# main_board.net
KiCad netlist of a schematic drawn in EAGLE
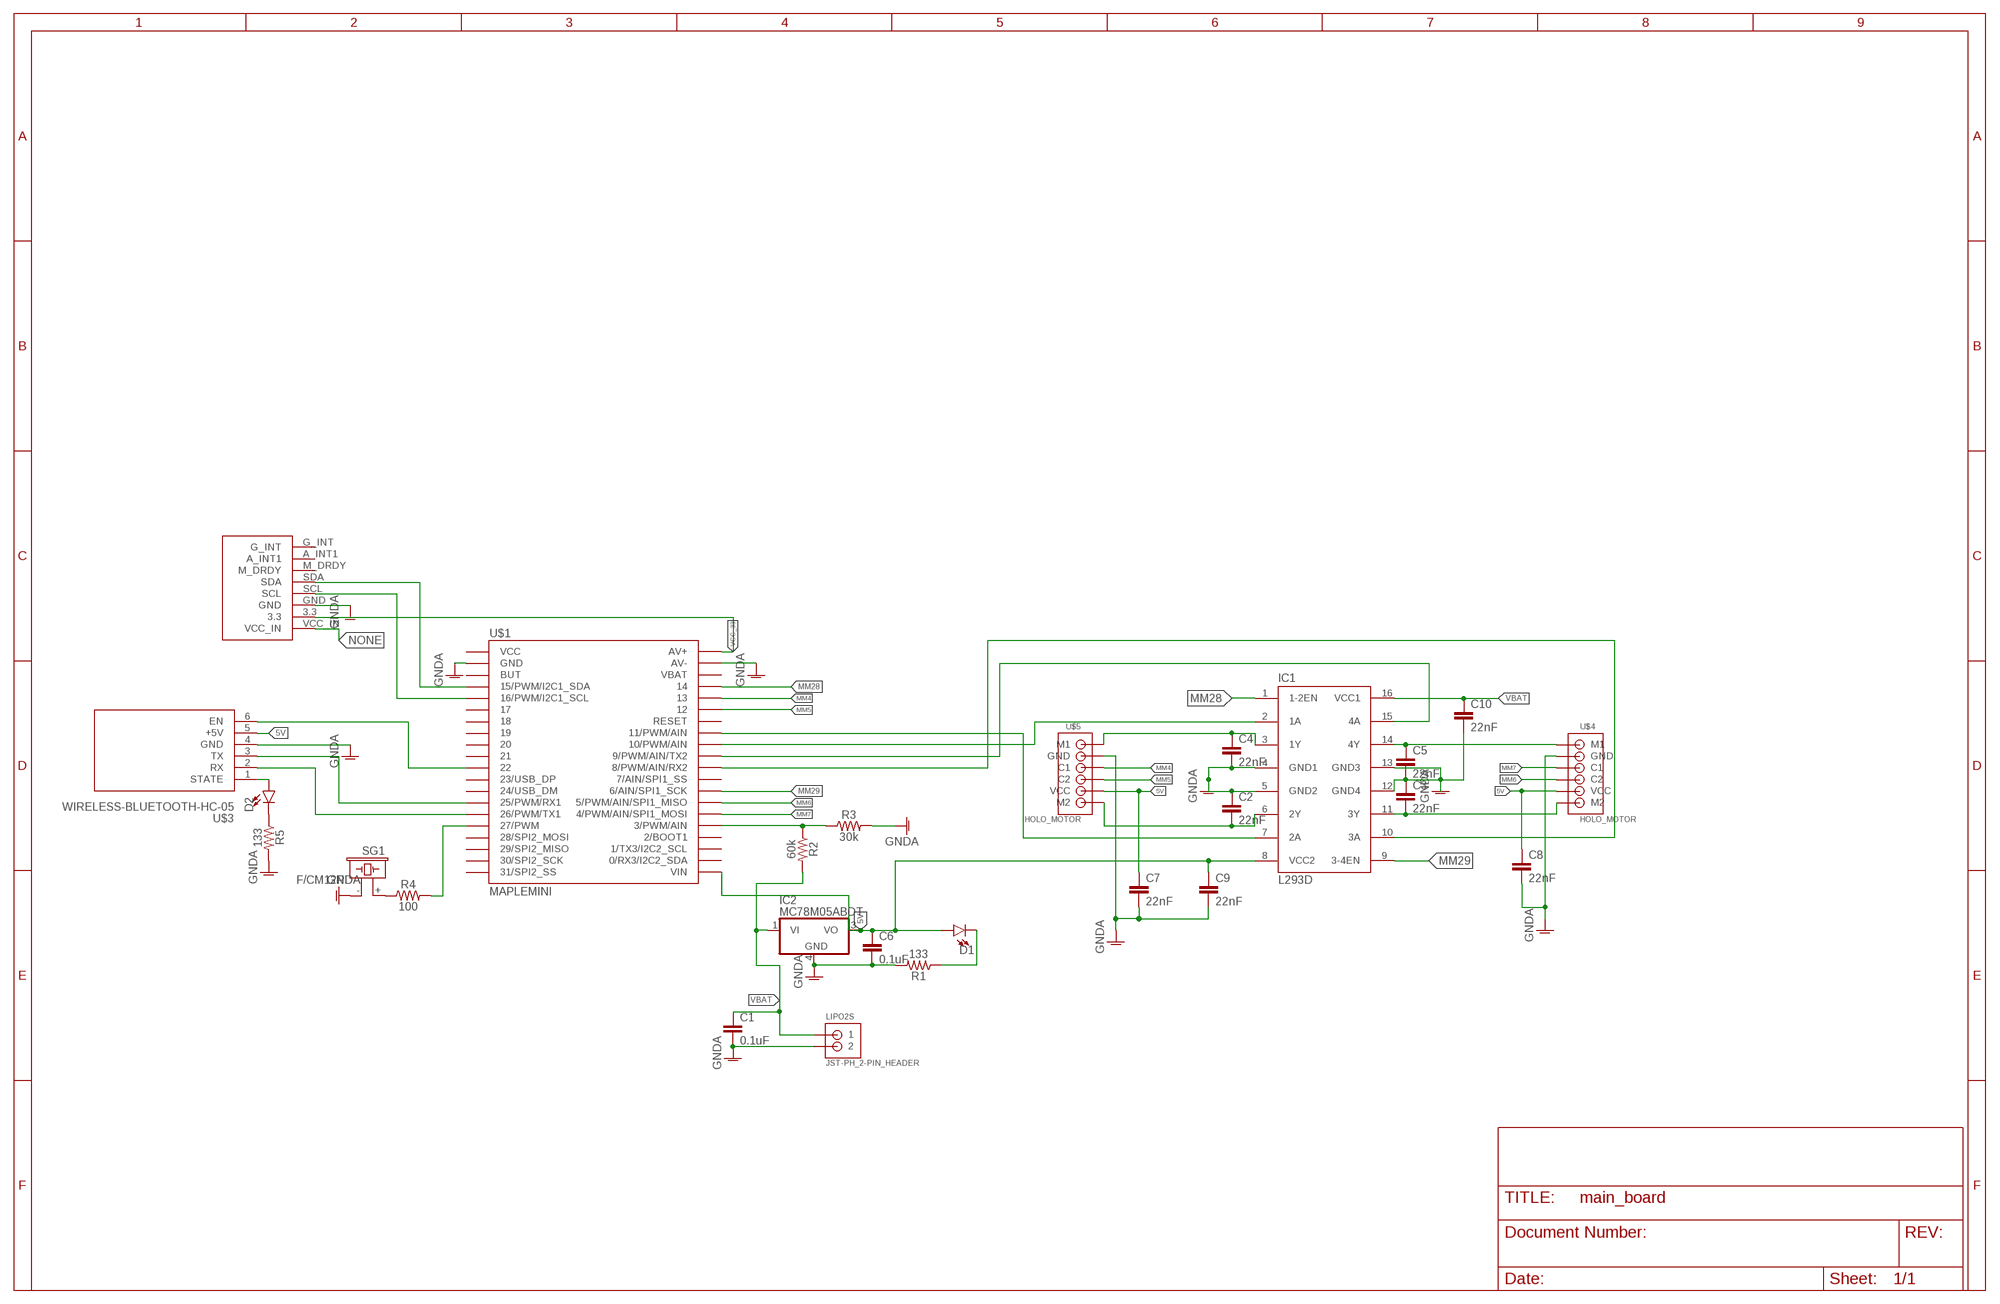
[diagram p0: schematic, sheet 1]

(export (version "E")
  (design (tool "Eeschema 10.0.6"))
  (components
    (comp (ref "C1")
      (value "0.1uF")
      (footprint "eagle-import:0603")
      (libsource (lib "eagle-import") (part "0.1UF-0603-25V-(+80/-20%)"))
    )
    (comp (ref "C2")
      (value "22nF")
      (footprint "eagle-import:0603")
      (libsource (lib "eagle-import") (part "22NF/22,000PF-0603-50V-10%"))
    )
    (comp (ref "C3")
      (value "22nF")
      (footprint "eagle-import:0603")
      (libsource (lib "eagle-import") (part "22NF/22,000PF-0603-50V-10%"))
    )
    (comp (ref "C4")
      (value "22nF")
      (footprint "eagle-import:0603")
      (libsource (lib "eagle-import") (part "22NF/22,000PF-0603-50V-10%"))
    )
    (comp (ref "C5")
      (value "22nF")
      (footprint "eagle-import:0603")
      (libsource (lib "eagle-import") (part "22NF/22,000PF-0603-50V-10%"))
    )
    (comp (ref "C6")
      (value "0.1uF")
      (footprint "eagle-import:0603")
      (libsource (lib "eagle-import") (part "0.1UF-0603-25V-(+80/-20%)"))
    )
    (comp (ref "C7")
      (value "22nF")
      (footprint "eagle-import:0603")
      (fields (field (name "PROD_ID") "CAP-07885"))
      (libsource (lib "eagle-import") (part "22NF/22,000PF-0603-50V-10%"))
    )
    (comp (ref "C8")
      (value "22nF")
      (footprint "eagle-import:0603")
      (fields (field (name "PROD_ID") "CAP-07885"))
      (libsource (lib "eagle-import") (part "22NF/22,000PF-0603-50V-10%"))
    )
    (comp (ref "C9")
      (value "22nF")
      (footprint "eagle-import:0603")
      (fields (field (name "PROD_ID") "CAP-07885"))
      (libsource (lib "eagle-import") (part "22NF/22,000PF-0603-50V-10%"))
    )
    (comp (ref "C10")
      (value "22nF")
      (footprint "eagle-import:0603")
      (fields (field (name "PROD_ID") "CAP-07885"))
      (libsource (lib "eagle-import") (part "22NF/22,000PF-0603-50V-10%"))
    )
    (comp (ref "D1")
      (value "LED-FKIT-1206")
      (footprint "eagle-import:FKIT-LED-1206")
      (libsource (lib "eagle-import") (part "LED-FKIT-1206"))
    )
    (comp (ref "D2")
      (value "LED-FKIT-1206")
      (footprint "eagle-import:FKIT-LED-1206")
      (libsource (lib "eagle-import") (part "LED-FKIT-1206"))
    )
    (comp (ref "IC1")
      (value "L293D")
      (footprint "eagle-import:DIL16")
      (libsource (lib "eagle-import") (part "L293D"))
    )
    (comp (ref "IC2")
      (value "MC78M05ABDT")
      (footprint "eagle-import:DPACK_3")
      (libsource (lib "eagle-import") (part "MC78M05ABDT"))
    )
    (comp (ref "LIPO2S")
      (value "JST-PH_2-PIN_HEADER")
      (footprint "eagle-import:JST_B2B-PH_HEADER")
      (libsource (lib "eagle-import") (part "JST-PH_2-PIN_HEADER"))
    )
    (comp (ref "R1")
      (value "133")
      (footprint "eagle-import:0603")
      (libsource (lib "eagle-import") (part "0.27OHM-0603-1/10W-1%"))
    )
    (comp (ref "R2")
      (value "60k")
      (footprint "eagle-import:0603")
      (libsource (lib "eagle-import") (part "0.27OHM-0603-1/10W-1%"))
    )
    (comp (ref "R3")
      (value "30k")
      (footprint "eagle-import:0603")
      (libsource (lib "eagle-import") (part "0.27OHM-0603-1/10W-1%"))
    )
    (comp (ref "R4")
      (value "100")
      (footprint "eagle-import:0603")
      (libsource (lib "eagle-import") (part "0.27OHM-0603-1/10W-1%"))
    )
    (comp (ref "R5")
      (value "133")
      (footprint "eagle-import:0603")
      (libsource (lib "eagle-import") (part "0.27OHM-0603-1/10W-1%"))
    )
    (comp (ref "SG1")
      (value "F/CM12P")
      (footprint "eagle-import:F_CM12P")
      (libsource (lib "eagle-import") (part "F/CM12P"))
    )
    (comp (ref "U$1")
      (value "MAPLEMINI")
      (footprint "eagle-import:20-DIP")
      (libsource (lib "eagle-import") (part "MAPLEMINI"))
    )
    (comp (ref "U$3")
      (value "WIRELESS-BLUETOOTH-HC-05")
      (footprint "eagle-import:WIRELESS-BLUETOOTH-HC-05")
      (libsource (lib "eagle-import") (part "WIRELESS-BLUETOOTH-HC-05"))
    )
    (comp (ref "U$4")
      (value "HOLO_MOTOR")
      (footprint "eagle-import:HOLO_MOTOR")
      (libsource (lib "eagle-import") (part "HOLO_MOTOR"))
    )
    (comp (ref "U$5")
      (value "HOLO_MOTOR")
      (footprint "eagle-import:HOLO_MOTOR")
      (libsource (lib "eagle-import") (part "HOLO_MOTOR"))
    )
    (comp (ref "U$6")
      (value "GY-85")
      (footprint "eagle-import:GY-85")
      (libsource (lib "eagle-import") (part "GY-85"))
    )
  )
  (nets
    (net (code "1") (name "5V") (class "Default")
      (node (ref "C6") (pin "1") (pinfunction "1_1") (pintype "passive"))
      (node (ref "C7") (pin "1") (pinfunction "1_1") (pintype "passive"))
      (node (ref "C8") (pin "1") (pinfunction "1_1") (pintype "passive"))
      (node (ref "C9") (pin "1") (pinfunction "1_1") (pintype "passive"))
      (node (ref "D1") (pin "A") (pinfunction "A_A") (pintype "passive"))
      (node (ref "IC1") (pin "8") (pinfunction "VCC2_8") (pintype "power_in"))
      (node (ref "IC2") (pin "3") (pinfunction "VO_3") (pintype "passive"))
      (node (ref "U$1") (pin "21") (pinfunction "VIN_21") (pintype "bidirectional"))
      (node (ref "U$3") (pin "5") (pinfunction "+5V_5") (pintype "power_in"))
      (node (ref "U$4") (pin "5") (pinfunction "VCC_5") (pintype "bidirectional"))
      (node (ref "U$5") (pin "5") (pinfunction "VCC_5") (pintype "bidirectional"))
    )
    (net (code "2") (name "GNDA") (class "Default")
      (node (ref "C1") (pin "2") (pinfunction "2_2") (pintype "passive"))
      (node (ref "C10") (pin "2") (pinfunction "2_2") (pintype "passive"))
      (node (ref "C2") (pin "1") (pinfunction "1_1") (pintype "passive"))
      (node (ref "C3") (pin "1") (pinfunction "1_1") (pintype "passive"))
      (node (ref "C4") (pin "2") (pinfunction "2_2") (pintype "passive"))
      (node (ref "C5") (pin "2") (pinfunction "2_2") (pintype "passive"))
      (node (ref "C6") (pin "2") (pinfunction "2_2") (pintype "passive"))
      (node (ref "C7") (pin "2") (pinfunction "2_2") (pintype "passive"))
      (node (ref "C8") (pin "2") (pinfunction "2_2") (pintype "passive"))
      (node (ref "C9") (pin "2") (pinfunction "2_2") (pintype "passive"))
      (node (ref "IC1") (pin "12") (pinfunction "GND4_12") (pintype "power_in"))
      (node (ref "IC1") (pin "13") (pinfunction "GND3_13") (pintype "power_in"))
      (node (ref "IC1") (pin "4") (pinfunction "GND1_4") (pintype "power_in"))
      (node (ref "IC1") (pin "5") (pinfunction "GND2_5") (pintype "power_in"))
      (node (ref "IC2") (pin "4") (pinfunction "GND_4") (pintype "passive"))
      (node (ref "LIPO2S") (pin "P2") (pinfunction "2_P2") (pintype "bidirectional"))
      (node (ref "R1") (pin "2") (pinfunction "2_2") (pintype "passive"))
      (node (ref "R3") (pin "2") (pinfunction "2_2") (pintype "passive"))
      (node (ref "R5") (pin "2") (pinfunction "2_2") (pintype "passive"))
      (node (ref "SG1") (pin "-") (pinfunction "2_-") (pintype "passive"))
      (node (ref "U$1") (pin "2") (pinfunction "GND_2") (pintype "bidirectional"))
      (node (ref "U$1") (pin "39") (pinfunction "AV-_39") (pintype "bidirectional"))
      (node (ref "U$3") (pin "4") (pinfunction "GND_4") (pintype "power_in"))
      (node (ref "U$4") (pin "2") (pinfunction "GND_2") (pintype "bidirectional"))
      (node (ref "U$5") (pin "2") (pinfunction "GND_2") (pintype "bidirectional"))
      (node (ref "U$6") (pin "GND") (pinfunction "GND_GND") (pintype "bidirectional"))
    )
    (net (code "3") (name "MM4") (class "Default")
      (node (ref "U$1") (pin "36") (pinfunction "13_36") (pintype "bidirectional"))
      (node (ref "U$5") (pin "3") (pinfunction "C1_3") (pintype "bidirectional"))
    )
    (net (code "4") (name "MM5") (class "Default")
      (node (ref "U$1") (pin "35") (pinfunction "12_35") (pintype "bidirectional"))
      (node (ref "U$5") (pin "4") (pinfunction "C2_4") (pintype "bidirectional"))
    )
    (net (code "5") (name "MM6") (class "Default")
      (node (ref "U$1") (pin "27") (pinfunction "5/PWM/AIN/SPI1_MISO_27") (pintype "bidirectional"))
      (node (ref "U$4") (pin "4") (pinfunction "C2_4") (pintype "bidirectional"))
    )
    (net (code "6") (name "MM7") (class "Default")
      (node (ref "U$1") (pin "26") (pinfunction "4/PWM/AIN/SPI1_MOSI_26") (pintype "bidirectional"))
      (node (ref "U$4") (pin "3") (pinfunction "C1_3") (pintype "bidirectional"))
    )
    (net (code "7") (name "MM28") (class "Default")
      (node (ref "IC1") (pin "1") (pinfunction "1-2EN_1") (pintype "input"))
      (node (ref "U$1") (pin "37") (pinfunction "14_37") (pintype "bidirectional"))
    )
    (net (code "8") (name "MM29") (class "Default")
      (node (ref "IC1") (pin "9") (pinfunction "3-4EN_9") (pintype "input"))
      (node (ref "U$1") (pin "28") (pinfunction "6/AIN/SPI1_SCK_28") (pintype "bidirectional"))
    )
    (net (code "9") (name "NONE") (class "Default")
      (node (ref "U$6") (pin "VCC_IN") (pinfunction "VCC_IN_VCC_IN") (pintype "bidirectional"))
    )
    (net (code "10") (name "Net-(D1-PadC)") (class "Default")
      (node (ref "D1") (pin "C") (pinfunction "C_C") (pintype "passive"))
      (node (ref "R1") (pin "1") (pinfunction "1_1") (pintype "passive"))
    )
    (net (code "11") (name "Net-(D2-PadC)") (class "Default")
      (node (ref "D2") (pin "C") (pinfunction "C_C") (pintype "passive"))
      (node (ref "R5") (pin "1") (pinfunction "1_1") (pintype "passive"))
    )
    (net (code "12") (name "Net-(IC1-1A)") (class "Default")
      (node (ref "IC1") (pin "2") (pinfunction "1A_2") (pintype "input"))
      (node (ref "U$1") (pin "32") (pinfunction "10/PWM/AIN_32") (pintype "bidirectional"))
    )
    (net (code "13") (name "Net-(IC1-1Y)") (class "Default")
      (node (ref "C4") (pin "1") (pinfunction "1_1") (pintype "passive"))
      (node (ref "IC1") (pin "3") (pinfunction "1Y_3") (pintype "output"))
      (node (ref "U$5") (pin "1") (pinfunction "M1_1") (pintype "bidirectional"))
    )
    (net (code "14") (name "Net-(IC1-2A)") (class "Default")
      (node (ref "IC1") (pin "7") (pinfunction "2A_7") (pintype "input"))
      (node (ref "U$1") (pin "33") (pinfunction "11/PWM/AIN_33") (pintype "bidirectional"))
    )
    (net (code "15") (name "Net-(IC1-2Y)") (class "Default")
      (node (ref "C2") (pin "2") (pinfunction "2_2") (pintype "passive"))
      (node (ref "IC1") (pin "6") (pinfunction "2Y_6") (pintype "output"))
      (node (ref "U$5") (pin "6") (pinfunction "M2_6") (pintype "bidirectional"))
    )
    (net (code "16") (name "Net-(IC1-3A)") (class "Default")
      (node (ref "IC1") (pin "10") (pinfunction "3A_10") (pintype "input"))
      (node (ref "U$1") (pin "30") (pinfunction "8/PWM/AIN/RX2_30") (pintype "bidirectional"))
    )
    (net (code "17") (name "Net-(IC1-3Y)") (class "Default")
      (node (ref "C3") (pin "2") (pinfunction "2_2") (pintype "passive"))
      (node (ref "IC1") (pin "11") (pinfunction "3Y_11") (pintype "output"))
      (node (ref "U$4") (pin "6") (pinfunction "M2_6") (pintype "bidirectional"))
    )
    (net (code "18") (name "Net-(IC1-4A)") (class "Default")
      (node (ref "IC1") (pin "15") (pinfunction "4A_15") (pintype "input"))
      (node (ref "U$1") (pin "31") (pinfunction "9/PWM/AIN/TX2_31") (pintype "bidirectional"))
    )
    (net (code "19") (name "Net-(IC1-4Y)") (class "Default")
      (node (ref "C5") (pin "1") (pinfunction "1_1") (pintype "passive"))
      (node (ref "IC1") (pin "14") (pinfunction "4Y_14") (pintype "output"))
      (node (ref "U$4") (pin "1") (pinfunction "M1_1") (pintype "bidirectional"))
    )
    (net (code "20") (name "Net-(SG1-1)") (class "Default")
      (node (ref "R4") (pin "1") (pinfunction "1_1") (pintype "passive"))
      (node (ref "SG1") (pin "+") (pinfunction "1_+") (pintype "passive"))
    )
    (net (code "21") (name "Net-(U$1-3{slash}PWM{slash}AIN)") (class "Default")
      (node (ref "R2") (pin "1") (pinfunction "1_1") (pintype "passive"))
      (node (ref "R3") (pin "1") (pinfunction "1_1") (pintype "passive"))
      (node (ref "U$1") (pin "25") (pinfunction "3/PWM/AIN_25") (pintype "bidirectional"))
    )
    (net (code "22") (name "Net-(U$1-15{slash}PWM{slash}I2C1_SDA)") (class "Default")
      (node (ref "U$1") (pin "4") (pinfunction "15/PWM/I2C1_SDA_4") (pintype "bidirectional"))
      (node (ref "U$6") (pin "SDA") (pinfunction "SDA_SDA") (pintype "bidirectional"))
    )
    (net (code "23") (name "Net-(U$1-16{slash}PWM{slash}I2C1_SCL)") (class "Default")
      (node (ref "U$1") (pin "5") (pinfunction "16/PWM/I2C1_SCL_5") (pintype "bidirectional"))
      (node (ref "U$6") (pin "SCL") (pinfunction "SCL_SCL") (pintype "bidirectional"))
    )
    (net (code "24") (name "Net-(U$1-22)") (class "Default")
      (node (ref "U$1") (pin "11") (pinfunction "22_11") (pintype "bidirectional"))
      (node (ref "U$3") (pin "6") (pinfunction "EN_6") (pintype "bidirectional"))
    )
    (net (code "25") (name "Net-(U$1-25{slash}PWM{slash}RX1)") (class "Default")
      (node (ref "U$1") (pin "14") (pinfunction "25/PWM/RX1_14") (pintype "bidirectional"))
      (node (ref "U$3") (pin "3") (pinfunction "TX_3") (pintype "bidirectional"))
    )
    (net (code "26") (name "Net-(U$1-26{slash}PWM{slash}TX1)") (class "Default")
      (node (ref "U$1") (pin "15") (pinfunction "26/PWM/TX1_15") (pintype "bidirectional"))
      (node (ref "U$3") (pin "2") (pinfunction "RX_2") (pintype "bidirectional"))
    )
    (net (code "27") (name "Net-(U$1-27{slash}PWM)") (class "Default")
      (node (ref "R4") (pin "2") (pinfunction "2_2") (pintype "passive"))
      (node (ref "U$1") (pin "16") (pinfunction "27/PWM_16") (pintype "bidirectional"))
    )
    (net (code "28") (name "Net-(U$3-STATE)") (class "Default")
      (node (ref "D2") (pin "A") (pinfunction "A_A") (pintype "passive"))
      (node (ref "U$3") (pin "1") (pinfunction "STATE_1") (pintype "bidirectional"))
    )
    (net (code "29") (name "VBAT") (class "Default")
      (node (ref "C1") (pin "1") (pinfunction "1_1") (pintype "passive"))
      (node (ref "C10") (pin "1") (pinfunction "1_1") (pintype "passive"))
      (node (ref "IC1") (pin "16") (pinfunction "VCC1_16") (pintype "power_in"))
      (node (ref "IC2") (pin "1") (pinfunction "VI_1") (pintype "input"))
      (node (ref "LIPO2S") (pin "P1") (pinfunction "1_P1") (pintype "bidirectional"))
      (node (ref "R2") (pin "2") (pinfunction "2_2") (pintype "passive"))
    )
    (net (code "30") (name "VCC_33") (class "Default")
      (node (ref "U$1") (pin "40") (pinfunction "AV+_40") (pintype "bidirectional"))
      (node (ref "U$6") (pin "3.3") (pinfunction "3.3_3.3") (pintype "bidirectional"))
    )
    (net (code "31") (name "unconnected-(U$1-0{slash}RX3{slash}I2C2_SDA-Pad22)") (class "Default")
      (node (ref "U$1") (pin "22") (pinfunction "0/RX3/I2C2_SDA_22") (pintype "bidirectional"))
    )
    (net (code "32") (name "unconnected-(U$1-1{slash}TX3{slash}I2C2_SCL-Pad23)") (class "Default")
      (node (ref "U$1") (pin "23") (pinfunction "1/TX3/I2C2_SCL_23") (pintype "bidirectional"))
    )
    (net (code "33") (name "unconnected-(U$1-2{slash}BOOT1-Pad24)") (class "Default")
      (node (ref "U$1") (pin "24") (pinfunction "2/BOOT1_24") (pintype "bidirectional"))
    )
    (net (code "34") (name "unconnected-(U$1-7{slash}AIN{slash}SPI1_SS-Pad29)") (class "Default")
      (node (ref "U$1") (pin "29") (pinfunction "7/AIN/SPI1_SS_29") (pintype "bidirectional"))
    )
    (net (code "35") (name "unconnected-(U$1-17-Pad6)") (class "Default")
      (node (ref "U$1") (pin "6") (pinfunction "17_6") (pintype "bidirectional"))
    )
    (net (code "36") (name "unconnected-(U$1-18-Pad7)") (class "Default")
      (node (ref "U$1") (pin "7") (pinfunction "18_7") (pintype "bidirectional"))
    )
    (net (code "37") (name "unconnected-(U$1-19-Pad8)") (class "Default")
      (node (ref "U$1") (pin "8") (pinfunction "19_8") (pintype "bidirectional"))
    )
    (net (code "38") (name "unconnected-(U$1-20-Pad9)") (class "Default")
      (node (ref "U$1") (pin "9") (pinfunction "20_9") (pintype "bidirectional"))
    )
    (net (code "39") (name "unconnected-(U$1-21-Pad10)") (class "Default")
      (node (ref "U$1") (pin "10") (pinfunction "21_10") (pintype "bidirectional"))
    )
    (net (code "40") (name "unconnected-(U$1-23{slash}USB_DP-Pad12)") (class "Default")
      (node (ref "U$1") (pin "12") (pinfunction "23/USB_DP_12") (pintype "bidirectional"))
    )
    (net (code "41") (name "unconnected-(U$1-24{slash}USB_DM-Pad13)") (class "Default")
      (node (ref "U$1") (pin "13") (pinfunction "24/USB_DM_13") (pintype "bidirectional"))
    )
    (net (code "42") (name "unconnected-(U$1-28{slash}SPI2_MOSI-Pad17)") (class "Default")
      (node (ref "U$1") (pin "17") (pinfunction "28/SPI2_MOSI_17") (pintype "bidirectional"))
    )
    (net (code "43") (name "unconnected-(U$1-29{slash}SPI2_MISO-Pad18)") (class "Default")
      (node (ref "U$1") (pin "18") (pinfunction "29/SPI2_MISO_18") (pintype "bidirectional"))
    )
    (net (code "44") (name "unconnected-(U$1-30{slash}SPI2_SCK-Pad19)") (class "Default")
      (node (ref "U$1") (pin "19") (pinfunction "30/SPI2_SCK_19") (pintype "bidirectional"))
    )
    (net (code "45") (name "unconnected-(U$1-31{slash}SPI2_SS-Pad20)") (class "Default")
      (node (ref "U$1") (pin "20") (pinfunction "31/SPI2_SS_20") (pintype "bidirectional"))
    )
    (net (code "46") (name "unconnected-(U$1-BUT-Pad3)") (class "Default")
      (node (ref "U$1") (pin "3") (pinfunction "BUT_3") (pintype "bidirectional"))
    )
    (net (code "47") (name "unconnected-(U$1-RESET-Pad34)") (class "Default")
      (node (ref "U$1") (pin "34") (pinfunction "RESET_34") (pintype "bidirectional"))
    )
    (net (code "48") (name "unconnected-(U$1-VBAT-Pad38)") (class "Default")
      (node (ref "U$1") (pin "38") (pinfunction "VBAT_38") (pintype "bidirectional"))
    )
    (net (code "49") (name "unconnected-(U$1-VCC-Pad1)") (class "Default")
      (node (ref "U$1") (pin "1") (pinfunction "VCC_1") (pintype "bidirectional"))
    )
    (net (code "50") (name "unconnected-(U$6-PadA_INT1)") (class "Default")
      (node (ref "U$6") (pin "A_INT1") (pinfunction "A_INT1_A_INT1") (pintype "bidirectional"))
    )
    (net (code "51") (name "unconnected-(U$6-PadG_INT)") (class "Default")
      (node (ref "U$6") (pin "G_INT") (pinfunction "G_INT_G_INT") (pintype "bidirectional"))
    )
    (net (code "52") (name "unconnected-(U$6-PadM_DRDY)") (class "Default")
      (node (ref "U$6") (pin "M_DRDY") (pinfunction "M_DRDY_M_DRDY") (pintype "bidirectional"))
    )
  )
)
